# 5_SDRAM.net
KiCad netlist of a schematic drawn in Altium Designer
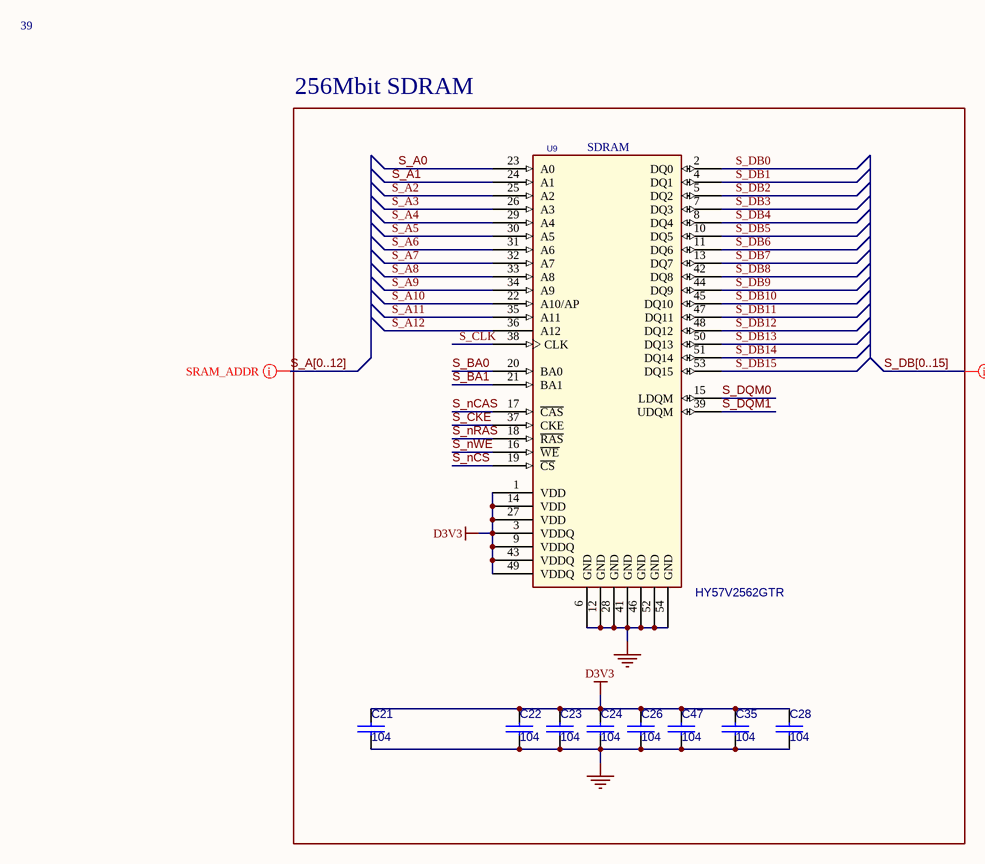
[diagram p0: 5_SDRAM.SchDoc]

(export (version "E")
  (design (tool "Eeschema 10.0.6"))
  (components
    (comp (ref "C21") (value "104") (libsource (lib "*") (part "C_Dup2")))
    (comp (ref "C22") (value "104") (libsource (lib "*") (part "C_Dup2")))
    (comp (ref "C23") (value "104") (libsource (lib "*") (part "C_Dup2")))
    (comp (ref "C24") (value "104") (libsource (lib "*") (part "C_Dup2")))
    (comp (ref "C26") (value "104") (libsource (lib "*") (part "C_Dup2")))
    (comp (ref "C28") (value "104") (libsource (lib "*") (part "C_Dup2")))
    (comp (ref "C35") (value "104") (libsource (lib "*") (part "C_Dup2")))
    (comp (ref "C47") (value "104") (libsource (lib "*") (part "C_Dup2")))
    (comp (ref "U9") (value "HY57V2562GTR") (libsource (lib "*") (part "HY57651620/SO_0")))
  )
  (nets
    (net (code "1") (name "/S_A0") (class "Default")
      (node (ref "U9") (pin "23") (pinfunction "A0_23") (pintype "input"))
    )
    (net (code "2") (name "/S_A1") (class "Default")
      (node (ref "U9") (pin "24") (pinfunction "A1_24") (pintype "input"))
    )
    (net (code "3") (name "/S_A2") (class "Default")
      (node (ref "U9") (pin "25") (pinfunction "A2_25") (pintype "input"))
    )
    (net (code "4") (name "/S_A3") (class "Default")
      (node (ref "U9") (pin "26") (pinfunction "A3_26") (pintype "input"))
    )
    (net (code "5") (name "/S_A4") (class "Default")
      (node (ref "U9") (pin "29") (pinfunction "A4_29") (pintype "input"))
    )
    (net (code "6") (name "/S_A5") (class "Default")
      (node (ref "U9") (pin "30") (pinfunction "A5_30") (pintype "input"))
    )
    (net (code "7") (name "/S_A6") (class "Default")
      (node (ref "U9") (pin "31") (pinfunction "A6_31") (pintype "input"))
    )
    (net (code "8") (name "/S_A7") (class "Default")
      (node (ref "U9") (pin "32") (pinfunction "A7_32") (pintype "input"))
    )
    (net (code "9") (name "/S_A8") (class "Default")
      (node (ref "U9") (pin "33") (pinfunction "A8_33") (pintype "input"))
    )
    (net (code "10") (name "/S_A9") (class "Default")
      (node (ref "U9") (pin "34") (pinfunction "A9_34") (pintype "input"))
    )
    (net (code "11") (name "/S_A10") (class "Default")
      (node (ref "U9") (pin "22") (pinfunction "A10/AP_22") (pintype "input"))
    )
    (net (code "12") (name "/S_A11") (class "Default")
      (node (ref "U9") (pin "35") (pinfunction "A11_35") (pintype "input"))
    )
    (net (code "13") (name "/S_A12") (class "Default")
      (node (ref "U9") (pin "36") (pinfunction "A12_36") (pintype "passive"))
    )
    (net (code "15") (name "/S_BA0") (class "Default")
      (node (ref "U9") (pin "20") (pinfunction "BA0_20") (pintype "input"))
    )
    (net (code "16") (name "/S_BA1") (class "Default")
      (node (ref "U9") (pin "21") (pinfunction "BA1_21") (pintype "input"))
    )
    (net (code "17") (name "/S_CKE") (class "Default")
      (node (ref "U9") (pin "37") (pinfunction "CKE_37") (pintype "input"))
    )
    (net (code "18") (name "/S_CLK") (class "Default")
      (node (ref "U9") (pin "38") (pinfunction "CLK_38") (pintype "input"))
    )
    (net (code "19") (name "/S_DB0") (class "Default")
      (node (ref "U9") (pin "2") (pinfunction "DQ0_2") (pintype "bidirectional"))
    )
    (net (code "20") (name "/S_DB1") (class "Default")
      (node (ref "U9") (pin "4") (pinfunction "DQ1_4") (pintype "bidirectional"))
    )
    (net (code "21") (name "/S_DB2") (class "Default")
      (node (ref "U9") (pin "5") (pinfunction "DQ2_5") (pintype "bidirectional"))
    )
    (net (code "22") (name "/S_DB3") (class "Default")
      (node (ref "U9") (pin "7") (pinfunction "DQ3_7") (pintype "bidirectional"))
    )
    (net (code "23") (name "/S_DB4") (class "Default")
      (node (ref "U9") (pin "8") (pinfunction "DQ4_8") (pintype "bidirectional"))
    )
    (net (code "24") (name "/S_DB5") (class "Default")
      (node (ref "U9") (pin "10") (pinfunction "DQ5_10") (pintype "bidirectional"))
    )
    (net (code "25") (name "/S_DB6") (class "Default")
      (node (ref "U9") (pin "11") (pinfunction "DQ6_11") (pintype "bidirectional"))
    )
    (net (code "26") (name "/S_DB7") (class "Default")
      (node (ref "U9") (pin "13") (pinfunction "DQ7_13") (pintype "bidirectional"))
    )
    (net (code "27") (name "/S_DB8") (class "Default")
      (node (ref "U9") (pin "42") (pinfunction "DQ8_42") (pintype "bidirectional"))
    )
    (net (code "28") (name "/S_DB9") (class "Default")
      (node (ref "U9") (pin "44") (pinfunction "DQ9_44") (pintype "bidirectional"))
    )
    (net (code "29") (name "/S_DB10") (class "Default")
      (node (ref "U9") (pin "45") (pinfunction "DQ10_45") (pintype "bidirectional"))
    )
    (net (code "30") (name "/S_DB11") (class "Default")
      (node (ref "U9") (pin "47") (pinfunction "DQ11_47") (pintype "bidirectional"))
    )
    (net (code "31") (name "/S_DB12") (class "Default")
      (node (ref "U9") (pin "48") (pinfunction "DQ12_48") (pintype "bidirectional"))
    )
    (net (code "32") (name "/S_DB13") (class "Default")
      (node (ref "U9") (pin "50") (pinfunction "DQ13_50") (pintype "bidirectional"))
    )
    (net (code "33") (name "/S_DB14") (class "Default")
      (node (ref "U9") (pin "51") (pinfunction "DQ14_51") (pintype "bidirectional"))
    )
    (net (code "34") (name "/S_DB15") (class "Default")
      (node (ref "U9") (pin "53") (pinfunction "DQ15_53") (pintype "bidirectional"))
    )
    (net (code "36") (name "/S_DQM0") (class "Default")
      (node (ref "U9") (pin "15") (pinfunction "LDQM_15") (pintype "bidirectional"))
    )
    (net (code "37") (name "/S_DQM1") (class "Default")
      (node (ref "U9") (pin "39") (pinfunction "UDQM_39") (pintype "bidirectional"))
    )
    (net (code "38") (name "/S_nCAS") (class "Default")
      (node (ref "U9") (pin "17") (pinfunction "~{CAS}_17") (pintype "input"))
    )
    (net (code "39") (name "/S_nCS") (class "Default")
      (node (ref "U9") (pin "19") (pinfunction "~{CS}_19") (pintype "input"))
    )
    (net (code "40") (name "/S_nRAS") (class "Default")
      (node (ref "U9") (pin "18") (pinfunction "~{RAS}_18") (pintype "input"))
    )
    (net (code "41") (name "/S_nWE") (class "Default")
      (node (ref "U9") (pin "16") (pinfunction "~{WE}_16") (pintype "input"))
    )
    (net (code "42") (name "D3V3") (class "Default")
      (node (ref "C21") (pin "1") (pinfunction "1_1") (pintype "passive"))
      (node (ref "C22") (pin "1") (pinfunction "1_1") (pintype "passive"))
      (node (ref "C23") (pin "1") (pinfunction "1_1") (pintype "passive"))
      (node (ref "C24") (pin "1") (pinfunction "1_1") (pintype "passive"))
      (node (ref "C26") (pin "1") (pinfunction "1_1") (pintype "passive"))
      (node (ref "C28") (pin "1") (pinfunction "1_1") (pintype "passive"))
      (node (ref "C35") (pin "1") (pinfunction "1_1") (pintype "passive"))
      (node (ref "C47") (pin "1") (pinfunction "1_1") (pintype "passive"))
      (node (ref "U9") (pin "1") (pinfunction "VDD_1") (pintype "power_in"))
      (node (ref "U9") (pin "14") (pinfunction "VDD_14") (pintype "power_in"))
      (node (ref "U9") (pin "27") (pinfunction "VDD_27") (pintype "power_in"))
      (node (ref "U9") (pin "3") (pinfunction "VDDQ_3") (pintype "power_in"))
      (node (ref "U9") (pin "43") (pinfunction "VDDQ_43") (pintype "power_in"))
      (node (ref "U9") (pin "49") (pinfunction "VDDQ_49") (pintype "power_in"))
      (node (ref "U9") (pin "9") (pinfunction "VDDQ_9") (pintype "power_in"))
    )
    (net (code "43") (name "GND") (class "Default")
      (node (ref "C21") (pin "2") (pinfunction "2_2") (pintype "passive"))
      (node (ref "C22") (pin "2") (pinfunction "2_2") (pintype "passive"))
      (node (ref "C23") (pin "2") (pinfunction "2_2") (pintype "passive"))
      (node (ref "C24") (pin "2") (pinfunction "2_2") (pintype "passive"))
      (node (ref "C26") (pin "2") (pinfunction "2_2") (pintype "passive"))
      (node (ref "C28") (pin "2") (pinfunction "2_2") (pintype "passive"))
      (node (ref "C35") (pin "2") (pinfunction "2_2") (pintype "passive"))
      (node (ref "C47") (pin "2") (pinfunction "2_2") (pintype "passive"))
      (node (ref "U9") (pin "12") (pinfunction "GND_12") (pintype "power_in"))
      (node (ref "U9") (pin "28") (pinfunction "GND_28") (pintype "power_in"))
      (node (ref "U9") (pin "41") (pinfunction "GND_41") (pintype "power_in"))
      (node (ref "U9") (pin "46") (pinfunction "GND_46") (pintype "power_in"))
      (node (ref "U9") (pin "52") (pinfunction "GND_52") (pintype "power_in"))
      (node (ref "U9") (pin "54") (pinfunction "GND_54") (pintype "power_in"))
      (node (ref "U9") (pin "6") (pinfunction "GND_6") (pintype "power_in"))
    )
  )
)
